# STM-connections.net
KiCad netlist of a schematic drawn in Altium Designer
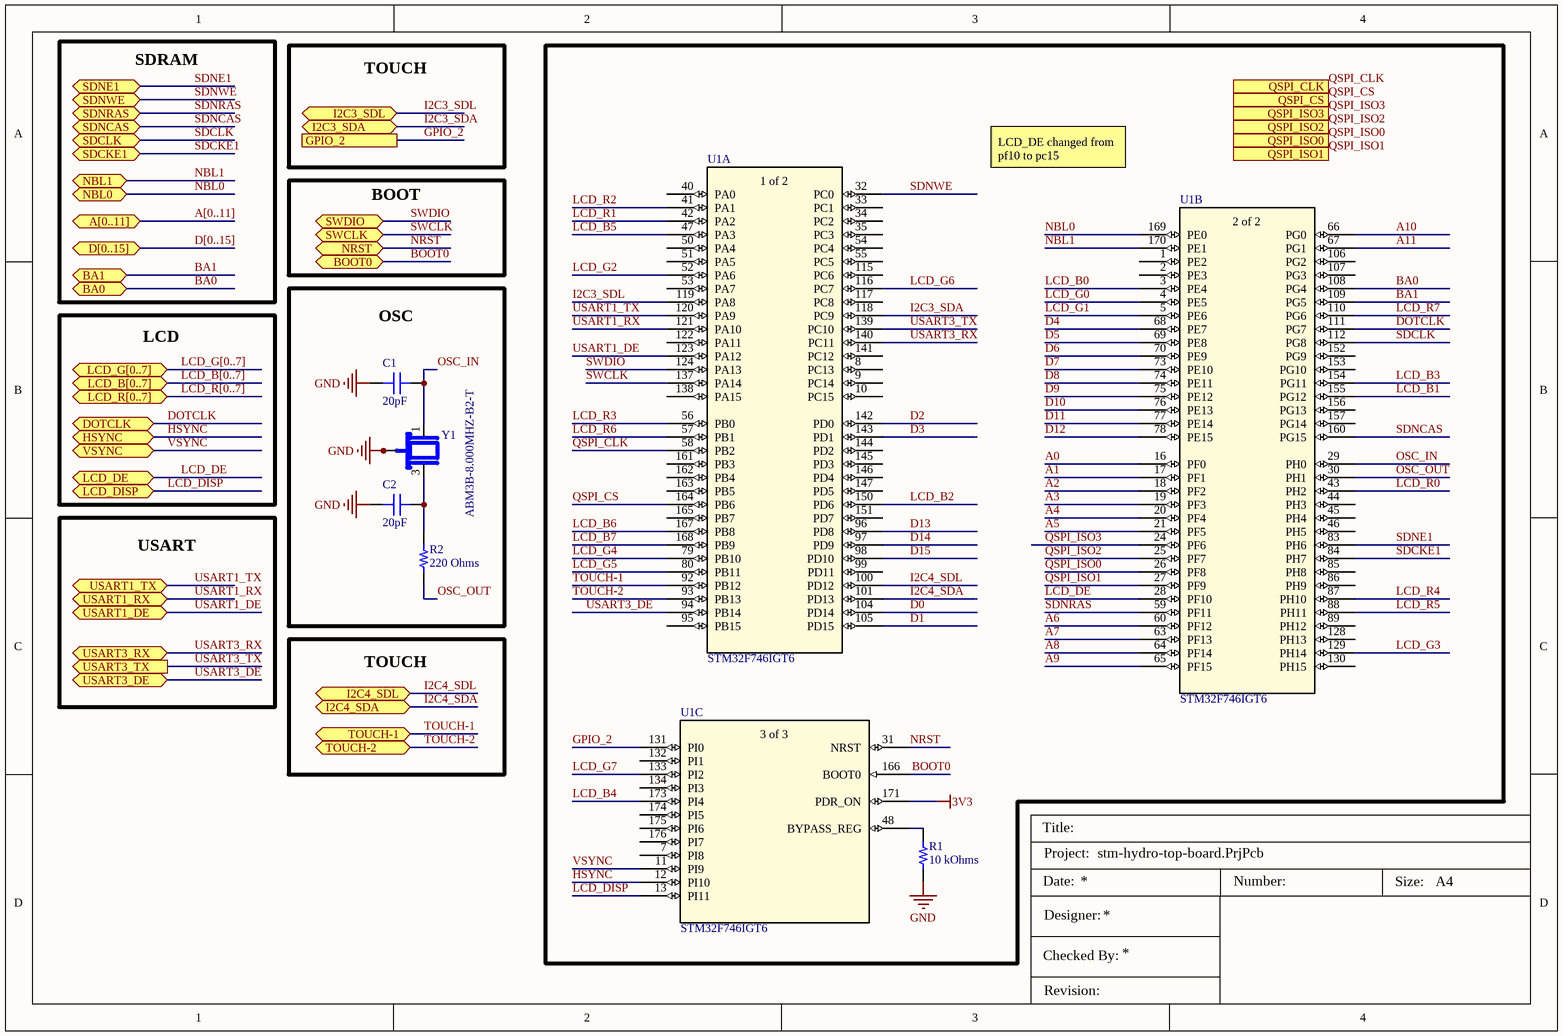
[diagram p0: STM-connections.SchDoc]

(export (version "E")
  (design (tool "Eeschema 10.0.6"))
  (components
    (comp (ref "C1")
      (value "20pF")
      (footprint "CAP 0603_1608")
      (description "CAP CER 20PF 100V C0G/NPO 0603")
      (fields (field (name "PART NUMBER") "CC0603JRNPO0BN200"))
      (libsource (lib "Celestial Altium Library - altium_library") (part "Capacitor"))
    )
    (comp (ref "C2")
      (value "20pF")
      (footprint "CAP 0603_1608")
      (description "CAP CER 20PF 100V C0G/NPO 0603")
      (fields (field (name "PART NUMBER") "CC0603JRNPO0BN200"))
      (libsource (lib "Celestial Altium Library - altium_library") (part "Capacitor"))
    )
    (comp (ref "R1")
      (value "10 kOhms")
      (footprint "RES 0603_1608")
      (description "RES SMD 10K OHM 1% 1/4W 0603")
      (fields (field (name "PART NUMBER") "CRCW060310K0FKEAHP"))
      (libsource (lib "Celestial Altium Library - altium_library") (part "Resistor"))
    )
    (comp (ref "R2")
      (value "220 Ohms")
      (footprint "RES 0603_1608")
      (description "RES SMD 220 OHM 5% 1/4W 0603")
      (fields (field (name "PART NUMBER") "CRCW0603220RJNEAHP"))
      (libsource (lib "Celestial Altium Library - altium_library") (part "Resistor"))
    )
    (comp (ref "U1")
      (value "STM32F746IGT6")
      (footprint "LQFP176_24X24_STM")
      (description "No Description Available")
      (fields (field (name "COPYRIGHT") "Copyright (C) 2018 Accelerated Designs. All rights reserved"))
      (libsource (lib "hy-smt") (part "STM32F746IGT6"))
    )
    (comp (ref "Y1")
      (value "ABM3B-8.000MHZ-B2-T")
      (footprint "OSC_ABM3B-8.000MHZ-B2-T")
      (description "8MHz Â±20ppm Crystal 18pF 200 Ohms 4-SMD, No Lead")
      (fields (field (name "MF") "Abracon"))
      (libsource (lib "Schlib1") (part "ABM3B-8.000MHZ-B2-T"))
    )
  )
  (nets
    (net (code "1") (name "/A0") (class "Default")
      (node (ref "U1") (pin "16") (pinfunction "PF0_16") (pintype "bidirectional"))
    )
    (net (code "2") (name "/A1") (class "Default")
      (node (ref "U1") (pin "17") (pinfunction "PF1_17") (pintype "bidirectional"))
    )
    (net (code "3") (name "/A2") (class "Default")
      (node (ref "U1") (pin "18") (pinfunction "PF2_18") (pintype "bidirectional"))
    )
    (net (code "4") (name "/A3") (class "Default")
      (node (ref "U1") (pin "19") (pinfunction "PF3_19") (pintype "bidirectional"))
    )
    (net (code "5") (name "/A4") (class "Default")
      (node (ref "U1") (pin "20") (pinfunction "PF4_20") (pintype "bidirectional"))
    )
    (net (code "6") (name "/A5") (class "Default")
      (node (ref "U1") (pin "21") (pinfunction "PF5_21") (pintype "bidirectional"))
    )
    (net (code "7") (name "/A6") (class "Default")
      (node (ref "U1") (pin "60") (pinfunction "PF12_60") (pintype "bidirectional"))
    )
    (net (code "8") (name "/A7") (class "Default")
      (node (ref "U1") (pin "63") (pinfunction "PF13_63") (pintype "bidirectional"))
    )
    (net (code "9") (name "/A8") (class "Default")
      (node (ref "U1") (pin "64") (pinfunction "PF14_64") (pintype "bidirectional"))
    )
    (net (code "10") (name "/A9") (class "Default")
      (node (ref "U1") (pin "65") (pinfunction "PF15_65") (pintype "bidirectional"))
    )
    (net (code "11") (name "/A10") (class "Default")
      (node (ref "U1") (pin "66") (pinfunction "PG0_66") (pintype "bidirectional"))
    )
    (net (code "12") (name "/A11") (class "Default")
      (node (ref "U1") (pin "67") (pinfunction "PG1_67") (pintype "bidirectional"))
    )
    (net (code "14") (name "/BA0") (class "Default")
      (node (ref "U1") (pin "108") (pinfunction "PG4_108") (pintype "bidirectional"))
    )
    (net (code "15") (name "/BA1") (class "Default")
      (node (ref "U1") (pin "109") (pinfunction "PG5_109") (pintype "bidirectional"))
    )
    (net (code "16") (name "/BOOT0") (class "Default")
      (node (ref "U1") (pin "166") (pinfunction "BOOT0_166") (pintype "input"))
    )
    (net (code "17") (name "/D0") (class "Default")
      (node (ref "U1") (pin "104") (pinfunction "PD14_104") (pintype "bidirectional"))
    )
    (net (code "18") (name "/D1") (class "Default")
      (node (ref "U1") (pin "105") (pinfunction "PD15_105") (pintype "bidirectional"))
    )
    (net (code "19") (name "/D2") (class "Default")
      (node (ref "U1") (pin "142") (pinfunction "PD0_142") (pintype "bidirectional"))
    )
    (net (code "20") (name "/D3") (class "Default")
      (node (ref "U1") (pin "143") (pinfunction "PD1_143") (pintype "bidirectional"))
    )
    (net (code "21") (name "/D4") (class "Default")
      (node (ref "U1") (pin "68") (pinfunction "PE7_68") (pintype "bidirectional"))
    )
    (net (code "22") (name "/D5") (class "Default")
      (node (ref "U1") (pin "69") (pinfunction "PE8_69") (pintype "bidirectional"))
    )
    (net (code "23") (name "/D6") (class "Default")
      (node (ref "U1") (pin "70") (pinfunction "PE9_70") (pintype "bidirectional"))
    )
    (net (code "24") (name "/D7") (class "Default")
      (node (ref "U1") (pin "73") (pinfunction "PE10_73") (pintype "bidirectional"))
    )
    (net (code "25") (name "/D8") (class "Default")
      (node (ref "U1") (pin "74") (pinfunction "PE11_74") (pintype "bidirectional"))
    )
    (net (code "26") (name "/D9") (class "Default")
      (node (ref "U1") (pin "75") (pinfunction "PE12_75") (pintype "bidirectional"))
    )
    (net (code "27") (name "/D10") (class "Default")
      (node (ref "U1") (pin "76") (pinfunction "PE13_76") (pintype "bidirectional"))
    )
    (net (code "28") (name "/D11") (class "Default")
      (node (ref "U1") (pin "77") (pinfunction "PE14_77") (pintype "bidirectional"))
    )
    (net (code "29") (name "/D12") (class "Default")
      (node (ref "U1") (pin "78") (pinfunction "PE15_78") (pintype "bidirectional"))
    )
    (net (code "30") (name "/D13") (class "Default")
      (node (ref "U1") (pin "96") (pinfunction "PD8_96") (pintype "bidirectional"))
    )
    (net (code "31") (name "/D14") (class "Default")
      (node (ref "U1") (pin "97") (pinfunction "PD9_97") (pintype "bidirectional"))
    )
    (net (code "32") (name "/D15") (class "Default")
      (node (ref "U1") (pin "98") (pinfunction "PD10_98") (pintype "bidirectional"))
    )
    (net (code "33") (name "/DOTCLK") (class "Default")
      (node (ref "U1") (pin "111") (pinfunction "PG7_111") (pintype "bidirectional"))
    )
    (net (code "35") (name "/GPIO_2") (class "Default")
      (node (ref "U1") (pin "131") (pinfunction "PI0_131") (pintype "bidirectional"))
    )
    (net (code "36") (name "/HSYNC") (class "Default")
      (node (ref "U1") (pin "12") (pinfunction "PI10_12") (pintype "bidirectional"))
    )
    (net (code "37") (name "/I2C3_SDA") (class "Default")
      (node (ref "U1") (pin "118") (pinfunction "PC9_118") (pintype "bidirectional"))
    )
    (net (code "38") (name "/I2C3_SDL") (class "Default")
      (node (ref "U1") (pin "119") (pinfunction "PA8_119") (pintype "bidirectional"))
    )
    (net (code "39") (name "/I2C4_SDA") (class "Default")
      (node (ref "U1") (pin "101") (pinfunction "PD13_101") (pintype "bidirectional"))
    )
    (net (code "40") (name "/I2C4_SDL") (class "Default")
      (node (ref "U1") (pin "100") (pinfunction "PD12_100") (pintype "bidirectional"))
    )
    (net (code "41") (name "/LCD_B0") (class "Default")
      (node (ref "U1") (pin "3") (pinfunction "PE4_3") (pintype "bidirectional"))
    )
    (net (code "42") (name "/LCD_B1") (class "Default")
      (node (ref "U1") (pin "155") (pinfunction "PG12_155") (pintype "bidirectional"))
    )
    (net (code "43") (name "/LCD_B2") (class "Default")
      (node (ref "U1") (pin "150") (pinfunction "PD6_150") (pintype "bidirectional"))
    )
    (net (code "44") (name "/LCD_B3") (class "Default")
      (node (ref "U1") (pin "154") (pinfunction "PG11_154") (pintype "bidirectional"))
    )
    (net (code "45") (name "/LCD_B4") (class "Default")
      (node (ref "U1") (pin "173") (pinfunction "PI4_173") (pintype "bidirectional"))
    )
    (net (code "46") (name "/LCD_B5") (class "Default")
      (node (ref "U1") (pin "47") (pinfunction "PA3_47") (pintype "bidirectional"))
    )
    (net (code "47") (name "/LCD_B6") (class "Default")
      (node (ref "U1") (pin "167") (pinfunction "PB8_167") (pintype "bidirectional"))
    )
    (net (code "48") (name "/LCD_B7") (class "Default")
      (node (ref "U1") (pin "168") (pinfunction "PB9_168") (pintype "bidirectional"))
    )
    (net (code "50") (name "/LCD_DE") (class "Default")
      (node (ref "U1") (pin "28") (pinfunction "PF10_28") (pintype "bidirectional"))
    )
    (net (code "51") (name "/LCD_DISP") (class "Default")
      (node (ref "U1") (pin "13") (pinfunction "PI11_13") (pintype "bidirectional"))
    )
    (net (code "52") (name "/LCD_G0") (class "Default")
      (node (ref "U1") (pin "4") (pinfunction "PE5_4") (pintype "bidirectional"))
    )
    (net (code "53") (name "/LCD_G1") (class "Default")
      (node (ref "U1") (pin "5") (pinfunction "PE6_5") (pintype "bidirectional"))
    )
    (net (code "54") (name "/LCD_G2") (class "Default")
      (node (ref "U1") (pin "52") (pinfunction "PA6_52") (pintype "bidirectional"))
    )
    (net (code "55") (name "/LCD_G3") (class "Default")
      (node (ref "U1") (pin "129") (pinfunction "PH14_129") (pintype "bidirectional"))
    )
    (net (code "56") (name "/LCD_G4") (class "Default")
      (node (ref "U1") (pin "79") (pinfunction "PB10_79") (pintype "bidirectional"))
    )
    (net (code "57") (name "/LCD_G5") (class "Default")
      (node (ref "U1") (pin "80") (pinfunction "PB11_80") (pintype "bidirectional"))
    )
    (net (code "58") (name "/LCD_G6") (class "Default")
      (node (ref "U1") (pin "116") (pinfunction "PC7_116") (pintype "bidirectional"))
    )
    (net (code "59") (name "/LCD_G7") (class "Default")
      (node (ref "U1") (pin "133") (pinfunction "PI2_133") (pintype "bidirectional"))
    )
    (net (code "61") (name "/LCD_R0") (class "Default")
      (node (ref "U1") (pin "43") (pinfunction "PH2_43") (pintype "bidirectional"))
    )
    (net (code "62") (name "/LCD_R1") (class "Default")
      (node (ref "U1") (pin "42") (pinfunction "PA2_42") (pintype "bidirectional"))
    )
    (net (code "63") (name "/LCD_R2") (class "Default")
      (node (ref "U1") (pin "41") (pinfunction "PA1_41") (pintype "bidirectional"))
    )
    (net (code "64") (name "/LCD_R3") (class "Default")
      (node (ref "U1") (pin "56") (pinfunction "PB0_56") (pintype "bidirectional"))
    )
    (net (code "65") (name "/LCD_R4") (class "Default")
      (node (ref "U1") (pin "87") (pinfunction "PH10_87") (pintype "bidirectional"))
    )
    (net (code "66") (name "/LCD_R5") (class "Default")
      (node (ref "U1") (pin "88") (pinfunction "PH11_88") (pintype "bidirectional"))
    )
    (net (code "67") (name "/LCD_R6") (class "Default")
      (node (ref "U1") (pin "57") (pinfunction "PB1_57") (pintype "bidirectional"))
    )
    (net (code "68") (name "/LCD_R7") (class "Default")
      (node (ref "U1") (pin "110") (pinfunction "PG6_110") (pintype "bidirectional"))
    )
    (net (code "70") (name "/NBL0") (class "Default")
      (node (ref "U1") (pin "169") (pinfunction "PE0_169") (pintype "bidirectional"))
    )
    (net (code "71") (name "/NBL1") (class "Default")
      (node (ref "U1") (pin "170") (pinfunction "PE1_170") (pintype "bidirectional"))
    )
    (net (code "72") (name "/NRST") (class "Default")
      (node (ref "U1") (pin "31") (pinfunction "NRST_31") (pintype "bidirectional"))
    )
    (net (code "73") (name "/OSC_IN") (class "Default")
      (node (ref "C1") (pin "2") (pinfunction "2_2") (pintype "passive"))
      (node (ref "U1") (pin "29") (pinfunction "PH0_29") (pintype "bidirectional"))
      (node (ref "Y1") (pin "1") (pinfunction "1_1") (pintype "passive"))
    )
    (net (code "74") (name "/OSC_OUT") (class "Default")
      (node (ref "R2") (pin "2") (pinfunction "2_2") (pintype "passive"))
      (node (ref "U1") (pin "30") (pinfunction "PH1_30") (pintype "bidirectional"))
    )
    (net (code "75") (name "/QSPI_CLK") (class "Default")
      (node (ref "U1") (pin "58") (pinfunction "PB2_58") (pintype "bidirectional"))
    )
    (net (code "76") (name "/QSPI_CS") (class "Default")
      (node (ref "U1") (pin "164") (pinfunction "PB6_164") (pintype "bidirectional"))
    )
    (net (code "77") (name "/QSPI_ISO0") (class "Default")
      (node (ref "U1") (pin "26") (pinfunction "PF8_26") (pintype "bidirectional"))
    )
    (net (code "78") (name "/QSPI_ISO1") (class "Default")
      (node (ref "U1") (pin "27") (pinfunction "PF9_27") (pintype "bidirectional"))
    )
    (net (code "79") (name "/QSPI_ISO2") (class "Default")
      (node (ref "U1") (pin "25") (pinfunction "PF7_25") (pintype "bidirectional"))
    )
    (net (code "80") (name "/QSPI_ISO3") (class "Default")
      (node (ref "U1") (pin "24") (pinfunction "PF6_24") (pintype "bidirectional"))
    )
    (net (code "81") (name "/SDCKE1") (class "Default")
      (node (ref "U1") (pin "84") (pinfunction "PH7_84") (pintype "bidirectional"))
    )
    (net (code "82") (name "/SDCLK") (class "Default")
      (node (ref "U1") (pin "112") (pinfunction "PG8_112") (pintype "bidirectional"))
    )
    (net (code "83") (name "/SDNCAS") (class "Default")
      (node (ref "U1") (pin "160") (pinfunction "PG15_160") (pintype "bidirectional"))
    )
    (net (code "84") (name "/SDNE1") (class "Default")
      (node (ref "U1") (pin "83") (pinfunction "PH6_83") (pintype "bidirectional"))
    )
    (net (code "85") (name "/SDNRAS") (class "Default")
      (node (ref "U1") (pin "59") (pinfunction "PF11_59") (pintype "bidirectional"))
    )
    (net (code "86") (name "/SDNWE") (class "Default")
      (node (ref "U1") (pin "32") (pinfunction "PC0_32") (pintype "bidirectional"))
    )
    (net (code "87") (name "/SWCLK") (class "Default")
      (node (ref "U1") (pin "137") (pinfunction "PA14_137") (pintype "bidirectional"))
    )
    (net (code "88") (name "/SWDIO") (class "Default")
      (node (ref "U1") (pin "124") (pinfunction "PA13_124") (pintype "bidirectional"))
    )
    (net (code "89") (name "/TOUCH-1") (class "Default")
      (node (ref "U1") (pin "92") (pinfunction "PB12_92") (pintype "bidirectional"))
    )
    (net (code "90") (name "/TOUCH-2") (class "Default")
      (node (ref "U1") (pin "93") (pinfunction "PB13_93") (pintype "bidirectional"))
    )
    (net (code "91") (name "/USART1_DE") (class "Default")
      (node (ref "U1") (pin "123") (pinfunction "PA12_123") (pintype "bidirectional"))
    )
    (net (code "92") (name "/USART1_RX") (class "Default")
      (node (ref "U1") (pin "121") (pinfunction "PA10_121") (pintype "bidirectional"))
    )
    (net (code "93") (name "/USART1_TX") (class "Default")
      (node (ref "U1") (pin "120") (pinfunction "PA9_120") (pintype "bidirectional"))
    )
    (net (code "94") (name "/USART3_DE") (class "Default")
      (node (ref "U1") (pin "94") (pinfunction "PB14_94") (pintype "bidirectional"))
    )
    (net (code "95") (name "/USART3_RX") (class "Default")
      (node (ref "U1") (pin "140") (pinfunction "PC11_140") (pintype "bidirectional"))
    )
    (net (code "96") (name "/USART3_TX") (class "Default")
      (node (ref "U1") (pin "139") (pinfunction "PC10_139") (pintype "bidirectional"))
    )
    (net (code "97") (name "/VSYNC") (class "Default")
      (node (ref "U1") (pin "11") (pinfunction "PI9_11") (pintype "bidirectional"))
    )
    (net (code "98") (name "3V3") (class "Default")
      (node (ref "U1") (pin "171") (pinfunction "PDR_ON_171") (pintype "bidirectional"))
    )
    (net (code "99") (name "GND") (class "Default")
      (node (ref "C1") (pin "1") (pinfunction "1_1") (pintype "passive"))
      (node (ref "C2") (pin "1") (pinfunction "1_1") (pintype "passive"))
      (node (ref "R1") (pin "1") (pinfunction "1_1") (pintype "passive"))
      (node (ref "Y1") (pin "2") (pinfunction "GND_2") (pintype "power_in"))
      (node (ref "Y1") (pin "4") (pinfunction "GND_4") (pintype "power_in"))
    )
    (net (code "100") (name "Net-(C2-Pad2)") (class "Default")
      (node (ref "C2") (pin "2") (pinfunction "2_2") (pintype "passive"))
      (node (ref "R2") (pin "1") (pinfunction "1_1") (pintype "passive"))
      (node (ref "Y1") (pin "3") (pinfunction "3_3") (pintype "passive"))
    )
    (net (code "101") (name "Net-(U1C-BYPASS_REG)") (class "Default")
      (node (ref "R1") (pin "2") (pinfunction "2_2") (pintype "passive"))
      (node (ref "U1") (pin "48") (pinfunction "BYPASS_REG_48") (pintype "bidirectional"))
    )
    (net (code "102") (name "unconnected-(U1A-PA0-Pad40)") (class "Default")
      (node (ref "U1") (pin "40") (pinfunction "PA0_40") (pintype "bidirectional"))
    )
    (net (code "103") (name "unconnected-(U1A-PA4-Pad50)") (class "Default")
      (node (ref "U1") (pin "50") (pinfunction "PA4_50") (pintype "bidirectional"))
    )
    (net (code "104") (name "unconnected-(U1A-PA5-Pad51)") (class "Default")
      (node (ref "U1") (pin "51") (pinfunction "PA5_51") (pintype "bidirectional"))
    )
    (net (code "105") (name "unconnected-(U1A-PA7-Pad53)") (class "Default")
      (node (ref "U1") (pin "53") (pinfunction "PA7_53") (pintype "bidirectional"))
    )
    (net (code "106") (name "unconnected-(U1A-PA11-Pad122)") (class "Default")
      (node (ref "U1") (pin "122") (pinfunction "PA11_122") (pintype "bidirectional"))
    )
    (net (code "107") (name "unconnected-(U1A-PA15-Pad138)") (class "Default")
      (node (ref "U1") (pin "138") (pinfunction "PA15_138") (pintype "bidirectional"))
    )
    (net (code "108") (name "unconnected-(U1A-PB3-Pad161)") (class "Default")
      (node (ref "U1") (pin "161") (pinfunction "PB3_161") (pintype "bidirectional"))
    )
    (net (code "109") (name "unconnected-(U1A-PB4-Pad162)") (class "Default")
      (node (ref "U1") (pin "162") (pinfunction "PB4_162") (pintype "bidirectional"))
    )
    (net (code "110") (name "unconnected-(U1A-PB5-Pad163)") (class "Default")
      (node (ref "U1") (pin "163") (pinfunction "PB5_163") (pintype "bidirectional"))
    )
    (net (code "111") (name "unconnected-(U1A-PB7-Pad165)") (class "Default")
      (node (ref "U1") (pin "165") (pinfunction "PB7_165") (pintype "bidirectional"))
    )
    (net (code "112") (name "unconnected-(U1A-PB15-Pad95)") (class "Default")
      (node (ref "U1") (pin "95") (pinfunction "PB15_95") (pintype "bidirectional"))
    )
    (net (code "113") (name "unconnected-(U1A-PC1-Pad33)") (class "Default")
      (node (ref "U1") (pin "33") (pinfunction "PC1_33") (pintype "bidirectional"))
    )
    (net (code "114") (name "unconnected-(U1A-PC2-Pad34)") (class "Default")
      (node (ref "U1") (pin "34") (pinfunction "PC2_34") (pintype "bidirectional"))
    )
    (net (code "115") (name "unconnected-(U1A-PC3-Pad35)") (class "Default")
      (node (ref "U1") (pin "35") (pinfunction "PC3_35") (pintype "bidirectional"))
    )
    (net (code "116") (name "unconnected-(U1A-PC4-Pad54)") (class "Default")
      (node (ref "U1") (pin "54") (pinfunction "PC4_54") (pintype "bidirectional"))
    )
    (net (code "117") (name "unconnected-(U1A-PC5-Pad55)") (class "Default")
      (node (ref "U1") (pin "55") (pinfunction "PC5_55") (pintype "bidirectional"))
    )
    (net (code "118") (name "unconnected-(U1A-PC6-Pad115)") (class "Default")
      (node (ref "U1") (pin "115") (pinfunction "PC6_115") (pintype "bidirectional"))
    )
    (net (code "119") (name "unconnected-(U1A-PC8-Pad117)") (class "Default")
      (node (ref "U1") (pin "117") (pinfunction "PC8_117") (pintype "bidirectional"))
    )
    (net (code "120") (name "unconnected-(U1A-PC12-Pad141)") (class "Default")
      (node (ref "U1") (pin "141") (pinfunction "PC12_141") (pintype "bidirectional"))
    )
    (net (code "121") (name "unconnected-(U1A-PC13-Pad8)") (class "Default")
      (node (ref "U1") (pin "8") (pinfunction "PC13_8") (pintype "bidirectional"))
    )
    (net (code "122") (name "unconnected-(U1A-PC14-Pad9)") (class "Default")
      (node (ref "U1") (pin "9") (pinfunction "PC14_9") (pintype "bidirectional"))
    )
    (net (code "123") (name "unconnected-(U1A-PC15-Pad10)") (class "Default")
      (node (ref "U1") (pin "10") (pinfunction "PC15_10") (pintype "bidirectional"))
    )
    (net (code "124") (name "unconnected-(U1A-PD2-Pad144)") (class "Default")
      (node (ref "U1") (pin "144") (pinfunction "PD2_144") (pintype "bidirectional"))
    )
    (net (code "125") (name "unconnected-(U1A-PD3-Pad145)") (class "Default")
      (node (ref "U1") (pin "145") (pinfunction "PD3_145") (pintype "bidirectional"))
    )
    (net (code "126") (name "unconnected-(U1A-PD4-Pad146)") (class "Default")
      (node (ref "U1") (pin "146") (pinfunction "PD4_146") (pintype "bidirectional"))
    )
    (net (code "127") (name "unconnected-(U1A-PD5-Pad147)") (class "Default")
      (node (ref "U1") (pin "147") (pinfunction "PD5_147") (pintype "bidirectional"))
    )
    (net (code "128") (name "unconnected-(U1A-PD7-Pad151)") (class "Default")
      (node (ref "U1") (pin "151") (pinfunction "PD7_151") (pintype "bidirectional"))
    )
    (net (code "129") (name "unconnected-(U1A-PD11-Pad99)") (class "Default")
      (node (ref "U1") (pin "99") (pinfunction "PD11_99") (pintype "bidirectional"))
    )
    (net (code "130") (name "unconnected-(U1B-PE2-Pad1)") (class "Default")
      (node (ref "U1") (pin "1") (pinfunction "PE2_1") (pintype "bidirectional"))
    )
    (net (code "131") (name "unconnected-(U1B-PE3-Pad2)") (class "Default")
      (node (ref "U1") (pin "2") (pinfunction "PE3_2") (pintype "bidirectional"))
    )
    (net (code "132") (name "unconnected-(U1B-PG2-Pad106)") (class "Default")
      (node (ref "U1") (pin "106") (pinfunction "PG2_106") (pintype "bidirectional"))
    )
    (net (code "133") (name "unconnected-(U1B-PG3-Pad107)") (class "Default")
      (node (ref "U1") (pin "107") (pinfunction "PG3_107") (pintype "bidirectional"))
    )
    (net (code "134") (name "unconnected-(U1B-PG9-Pad152)") (class "Default")
      (node (ref "U1") (pin "152") (pinfunction "PG9_152") (pintype "bidirectional"))
    )
    (net (code "135") (name "unconnected-(U1B-PG10-Pad153)") (class "Default")
      (node (ref "U1") (pin "153") (pinfunction "PG10_153") (pintype "bidirectional"))
    )
    (net (code "136") (name "unconnected-(U1B-PG13-Pad156)") (class "Default")
      (node (ref "U1") (pin "156") (pinfunction "PG13_156") (pintype "bidirectional"))
    )
    (net (code "137") (name "unconnected-(U1B-PG14-Pad157)") (class "Default")
      (node (ref "U1") (pin "157") (pinfunction "PG14_157") (pintype "bidirectional"))
    )
    (net (code "138") (name "unconnected-(U1B-PH3-Pad44)") (class "Default")
      (node (ref "U1") (pin "44") (pinfunction "PH3_44") (pintype "bidirectional"))
    )
    (net (code "139") (name "unconnected-(U1B-PH4-Pad45)") (class "Default")
      (node (ref "U1") (pin "45") (pinfunction "PH4_45") (pintype "bidirectional"))
    )
    (net (code "140") (name "unconnected-(U1B-PH5-Pad46)") (class "Default")
      (node (ref "U1") (pin "46") (pinfunction "PH5_46") (pintype "bidirectional"))
    )
    (net (code "141") (name "unconnected-(U1B-PH8-Pad85)") (class "Default")
      (node (ref "U1") (pin "85") (pinfunction "PH8_85") (pintype "bidirectional"))
    )
    (net (code "142") (name "unconnected-(U1B-PH9-Pad86)") (class "Default")
      (node (ref "U1") (pin "86") (pinfunction "PH9_86") (pintype "bidirectional"))
    )
    (net (code "143") (name "unconnected-(U1B-PH12-Pad89)") (class "Default")
      (node (ref "U1") (pin "89") (pinfunction "PH12_89") (pintype "bidirectional"))
    )
    (net (code "144") (name "unconnected-(U1B-PH13-Pad128)") (class "Default")
      (node (ref "U1") (pin "128") (pinfunction "PH13_128") (pintype "bidirectional"))
    )
    (net (code "145") (name "unconnected-(U1B-PH15-Pad130)") (class "Default")
      (node (ref "U1") (pin "130") (pinfunction "PH15_130") (pintype "bidirectional"))
    )
    (net (code "146") (name "unconnected-(U1C-PI1-Pad132)") (class "Default")
      (node (ref "U1") (pin "132") (pinfunction "PI1_132") (pintype "bidirectional"))
    )
    (net (code "147") (name "unconnected-(U1C-PI3-Pad134)") (class "Default")
      (node (ref "U1") (pin "134") (pinfunction "PI3_134") (pintype "bidirectional"))
    )
    (net (code "148") (name "unconnected-(U1C-PI5-Pad174)") (class "Default")
      (node (ref "U1") (pin "174") (pinfunction "PI5_174") (pintype "bidirectional"))
    )
    (net (code "149") (name "unconnected-(U1C-PI6-Pad175)") (class "Default")
      (node (ref "U1") (pin "175") (pinfunction "PI6_175") (pintype "bidirectional"))
    )
    (net (code "150") (name "unconnected-(U1C-PI7-Pad176)") (class "Default")
      (node (ref "U1") (pin "176") (pinfunction "PI7_176") (pintype "bidirectional"))
    )
    (net (code "151") (name "unconnected-(U1C-PI8-Pad7)") (class "Default")
      (node (ref "U1") (pin "7") (pinfunction "PI8_7") (pintype "bidirectional"))
    )
  )
)
